# NeuroILO.net
KiCad netlist of a schematic drawn in Altium Designer
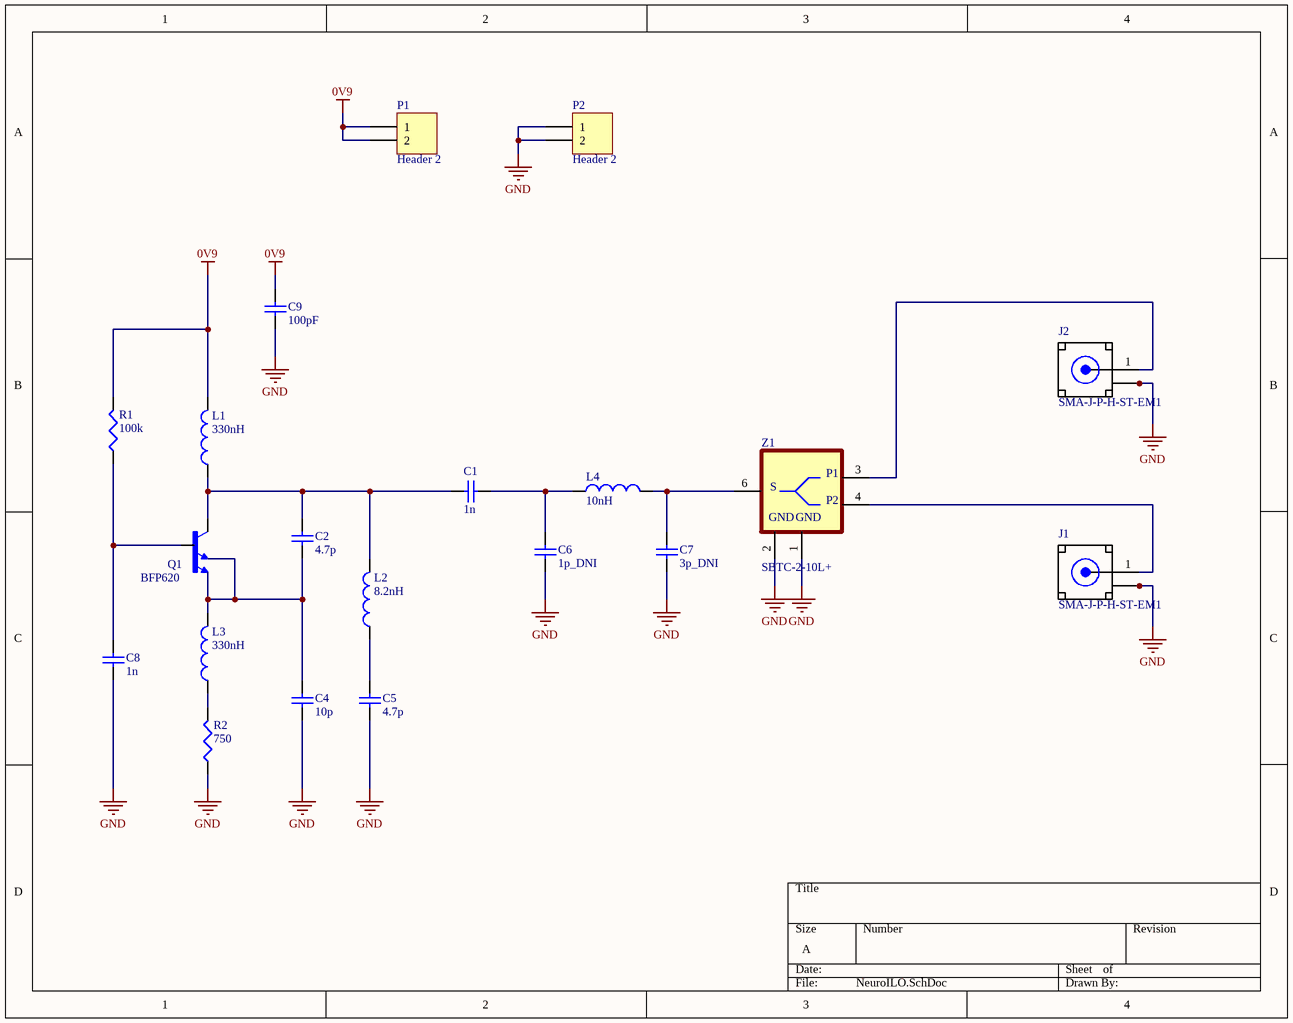
[diagram p0: NeuroILO.SchDoc]

(export (version "E")
  (design (tool "Eeschema 10.0.6"))
  (components
    (comp (ref "C1")
      (value "1n")
      (footprint "SMD-0603")
      (description "Ceramic Capacitor 0603")
      (libsource (lib "LCR") (part "CAP0603"))
    )
    (comp (ref "C2")
      (value "4.7p")
      (footprint "SMD-0603")
      (description "Ceramic Capacitor 0603")
      (libsource (lib "LCR") (part "CAP0603"))
    )
    (comp (ref "C4")
      (value "10p")
      (footprint "SMD-0603")
      (description "Ceramic Capacitor 0603")
      (libsource (lib "LCR") (part "CAP0603"))
    )
    (comp (ref "C5")
      (value "4.7p")
      (footprint "SMD-0603")
      (description "Ceramic Capacitor 0603")
      (libsource (lib "LCR") (part "CAP0603"))
    )
    (comp (ref "C6")
      (value "1p_DNI")
      (footprint "SMD-0603")
      (description "Ceramic Capacitor 0603")
      (libsource (lib "LCR") (part "CAP0603"))
    )
    (comp (ref "C7")
      (value "3p_DNI")
      (footprint "SMD-0603")
      (description "Ceramic Capacitor 0603")
      (libsource (lib "LCR") (part "CAP0603"))
    )
    (comp (ref "C8")
      (value "1n")
      (footprint "SMD-0603")
      (description "Ceramic Capacitor 0603")
      (libsource (lib "LCR") (part "CAP0603"))
    )
    (comp (ref "C9")
      (value "100pF")
      (footprint "SMD-0603")
      (description "Ceramic Capacitor 0603")
      (libsource (lib "LCR") (part "CAP0603"))
    )
    (comp (ref "J1")
      (value "SMA-J-P-H-ST-EM1")
      (footprint "SMA-J-P-H-ST-EM1")
      (description "Connector SMA F 50Ohm Solder ST Edge Mount Gold Over Nickel Tray")
      (fields (field (name "MF") "Samtec"))
      (libsource (lib "Connectors") (part "SMA-J-P-H-ST-EM1"))
    )
    (comp (ref "J2")
      (value "SMA-J-P-H-ST-EM1")
      (footprint "SMA-J-P-H-ST-EM1")
      (description "Connector SMA F 50Ohm Solder ST Edge Mount Gold Over Nickel Tray")
      (fields (field (name "MF") "Samtec"))
      (libsource (lib "Connectors") (part "SMA-J-P-H-ST-EM1"))
    )
    (comp (ref "L1")
      (value "330nH")
      (footprint "SMD-0603")
      (description "Inductor 0603")
      (libsource (lib "LCR") (part "L0603"))
    )
    (comp (ref "L2")
      (value "8.2nH")
      (footprint "SMD-0603")
      (description "Inductor 0603")
      (libsource (lib "LCR") (part "L0603"))
    )
    (comp (ref "L3")
      (value "330nH")
      (footprint "SMD-0603")
      (description "Inductor 0603")
      (libsource (lib "LCR") (part "L0603"))
    )
    (comp (ref "L4")
      (value "10nH")
      (footprint "SMD-0603")
      (description "Inductor 0603")
      (libsource (lib "LCR") (part "L0603"))
    )
    (comp (ref "P1")
      (value "Header 2")
      (footprint "HDR1X2")
      (description "Header, 2-Pin")
      (fields (field (name "PUBLISHER") "Altium Limited"))
      (libsource (lib "Miscellaneous Connectors") (part "Header 2"))
    )
    (comp (ref "P2")
      (value "Header 2")
      (footprint "HDR1X2")
      (description "Header, 2-Pin")
      (fields (field (name "PUBLISHER") "Altium Limited"))
      (libsource (lib "Miscellaneous Connectors") (part "Header 2"))
    )
    (comp (ref "Q1")
      (value "BFP620")
      (footprint "SOT343")
      (description "Trans RF BJT NPN 2.3V 0.08A 185mW Automotive 4-Pin(3+Tab) SOT-343 T/R")
      (fields (field (name "MF") "Infineon Technologies"))
      (libsource (lib "BFP620") (part "BFP620"))
    )
    (comp (ref "R1")
      (value "100k")
      (footprint "SMD-0603")
      (description "Resistor-0603")
      (libsource (lib "LCR") (part "RES0603"))
    )
    (comp (ref "R2")
      (value "750")
      (footprint "SMD-0603")
      (description "Resistor-0603")
      (libsource (lib "LCR") (part "RES0603"))
    )
    (comp (ref "Z1")
      (value "SBTC-2-10L+")
      (footprint "AT1029")
      (description "Power Divider, 2 Way-0 , 0.005 to 1.0 GHz, 50 ohms, SMT")
      (fields (field (name "MF") "Mini-Circuits"))
      (libsource (lib "SBTC-2-10L_") (part "SBTC-2-10L+"))
    )
  )
  (nets
    (net (code "1") (name "0V9") (class "Default")
      (node (ref "C9") (pin "2") (pinfunction "2_2") (pintype "passive"))
      (node (ref "L1") (pin "2") (pinfunction "2_2") (pintype "passive"))
      (node (ref "P1") (pin "1") (pinfunction "1_1") (pintype "passive"))
      (node (ref "P1") (pin "2") (pinfunction "2_2") (pintype "passive"))
      (node (ref "R1") (pin "2") (pinfunction "2_2") (pintype "passive"))
    )
    (net (code "2") (name "GND") (class "Default")
      (node (ref "C4") (pin "1") (pinfunction "1_1") (pintype "passive"))
      (node (ref "C5") (pin "1") (pinfunction "1_1") (pintype "passive"))
      (node (ref "C6") (pin "1") (pinfunction "1_1") (pintype "passive"))
      (node (ref "C7") (pin "1") (pinfunction "1_1") (pintype "passive"))
      (node (ref "C8") (pin "1") (pinfunction "1_1") (pintype "passive"))
      (node (ref "C9") (pin "1") (pinfunction "1_1") (pintype "passive"))
      (node (ref "J1") (pin "2_1") (pinfunction "GND_2_1") (pintype "power_in"))
      (node (ref "J1") (pin "2_2") (pinfunction "GND_2_2") (pintype "power_in"))
      (node (ref "J1") (pin "3_1") (pinfunction "GND_3_1") (pintype "power_in"))
      (node (ref "J1") (pin "3_2") (pinfunction "GND_3_2") (pintype "power_in"))
      (node (ref "J2") (pin "2_1") (pinfunction "GND_2_1") (pintype "power_in"))
      (node (ref "J2") (pin "2_2") (pinfunction "GND_2_2") (pintype "power_in"))
      (node (ref "J2") (pin "3_1") (pinfunction "GND_3_1") (pintype "power_in"))
      (node (ref "J2") (pin "3_2") (pinfunction "GND_3_2") (pintype "power_in"))
      (node (ref "P2") (pin "1") (pinfunction "1_1") (pintype "passive"))
      (node (ref "P2") (pin "2") (pinfunction "2_2") (pintype "passive"))
      (node (ref "R2") (pin "1") (pinfunction "1_1") (pintype "passive"))
      (node (ref "Z1") (pin "1") (pinfunction "GND2_1") (pintype "passive"))
      (node (ref "Z1") (pin "2") (pinfunction "GND1_2") (pintype "passive"))
    )
    (net (code "3") (name "Net-(C1-Pad1)") (class "Default")
      (node (ref "C1") (pin "1") (pinfunction "1_1") (pintype "passive"))
      (node (ref "C6") (pin "2") (pinfunction "2_2") (pintype "passive"))
      (node (ref "L4") (pin "1") (pinfunction "1_1") (pintype "passive"))
    )
    (net (code "4") (name "Net-(C5-Pad2)") (class "Default")
      (node (ref "C5") (pin "2") (pinfunction "2_2") (pintype "passive"))
      (node (ref "L2") (pin "1") (pinfunction "1_1") (pintype "passive"))
    )
    (net (code "5") (name "Net-(J1-SIGNAL)") (class "Default")
      (node (ref "J1") (pin "1") (pinfunction "SIGNAL_1") (pintype "passive"))
      (node (ref "Z1") (pin "4") (pinfunction "P2_4") (pintype "passive"))
    )
    (net (code "6") (name "Net-(J2-SIGNAL)") (class "Default")
      (node (ref "J2") (pin "1") (pinfunction "SIGNAL_1") (pintype "passive"))
      (node (ref "Z1") (pin "3") (pinfunction "P1_3") (pintype "passive"))
    )
    (net (code "7") (name "Net-(L3-Pad1)") (class "Default")
      (node (ref "L3") (pin "1") (pinfunction "1_1") (pintype "passive"))
      (node (ref "R2") (pin "2") (pinfunction "2_2") (pintype "passive"))
    )
    (net (code "8") (name "Net-(Q1-B)") (class "Default")
      (node (ref "C8") (pin "2") (pinfunction "2_2") (pintype "passive"))
      (node (ref "Q1") (pin "1") (pinfunction "B_1") (pintype "passive"))
      (node (ref "R1") (pin "1") (pinfunction "1_1") (pintype "passive"))
    )
    (net (code "9") (name "Net-(Q1-C)") (class "Default")
      (node (ref "C1") (pin "2") (pinfunction "2_2") (pintype "passive"))
      (node (ref "C2") (pin "2") (pinfunction "2_2") (pintype "passive"))
      (node (ref "L1") (pin "1") (pinfunction "1_1") (pintype "passive"))
      (node (ref "L2") (pin "2") (pinfunction "2_2") (pintype "passive"))
      (node (ref "Q1") (pin "3") (pinfunction "C_3") (pintype "passive"))
    )
    (net (code "10") (name "Net-(Q1-E1)") (class "Default")
      (node (ref "C2") (pin "1") (pinfunction "1_1") (pintype "passive"))
      (node (ref "C4") (pin "2") (pinfunction "2_2") (pintype "passive"))
      (node (ref "L3") (pin "2") (pinfunction "2_2") (pintype "passive"))
      (node (ref "Q1") (pin "2") (pinfunction "E1_2") (pintype "passive"))
      (node (ref "Q1") (pin "4") (pinfunction "E2_4") (pintype "passive"))
    )
    (net (code "11") (name "Net-(Z1-S)") (class "Default")
      (node (ref "C7") (pin "2") (pinfunction "2_2") (pintype "passive"))
      (node (ref "L4") (pin "2") (pinfunction "2_2") (pintype "passive"))
      (node (ref "Z1") (pin "6") (pinfunction "S_6") (pintype "passive"))
    )
  )
)
